# SNES-1Chip_MR_QID.net
KiCad netlist of a schematic drawn in EAGLE
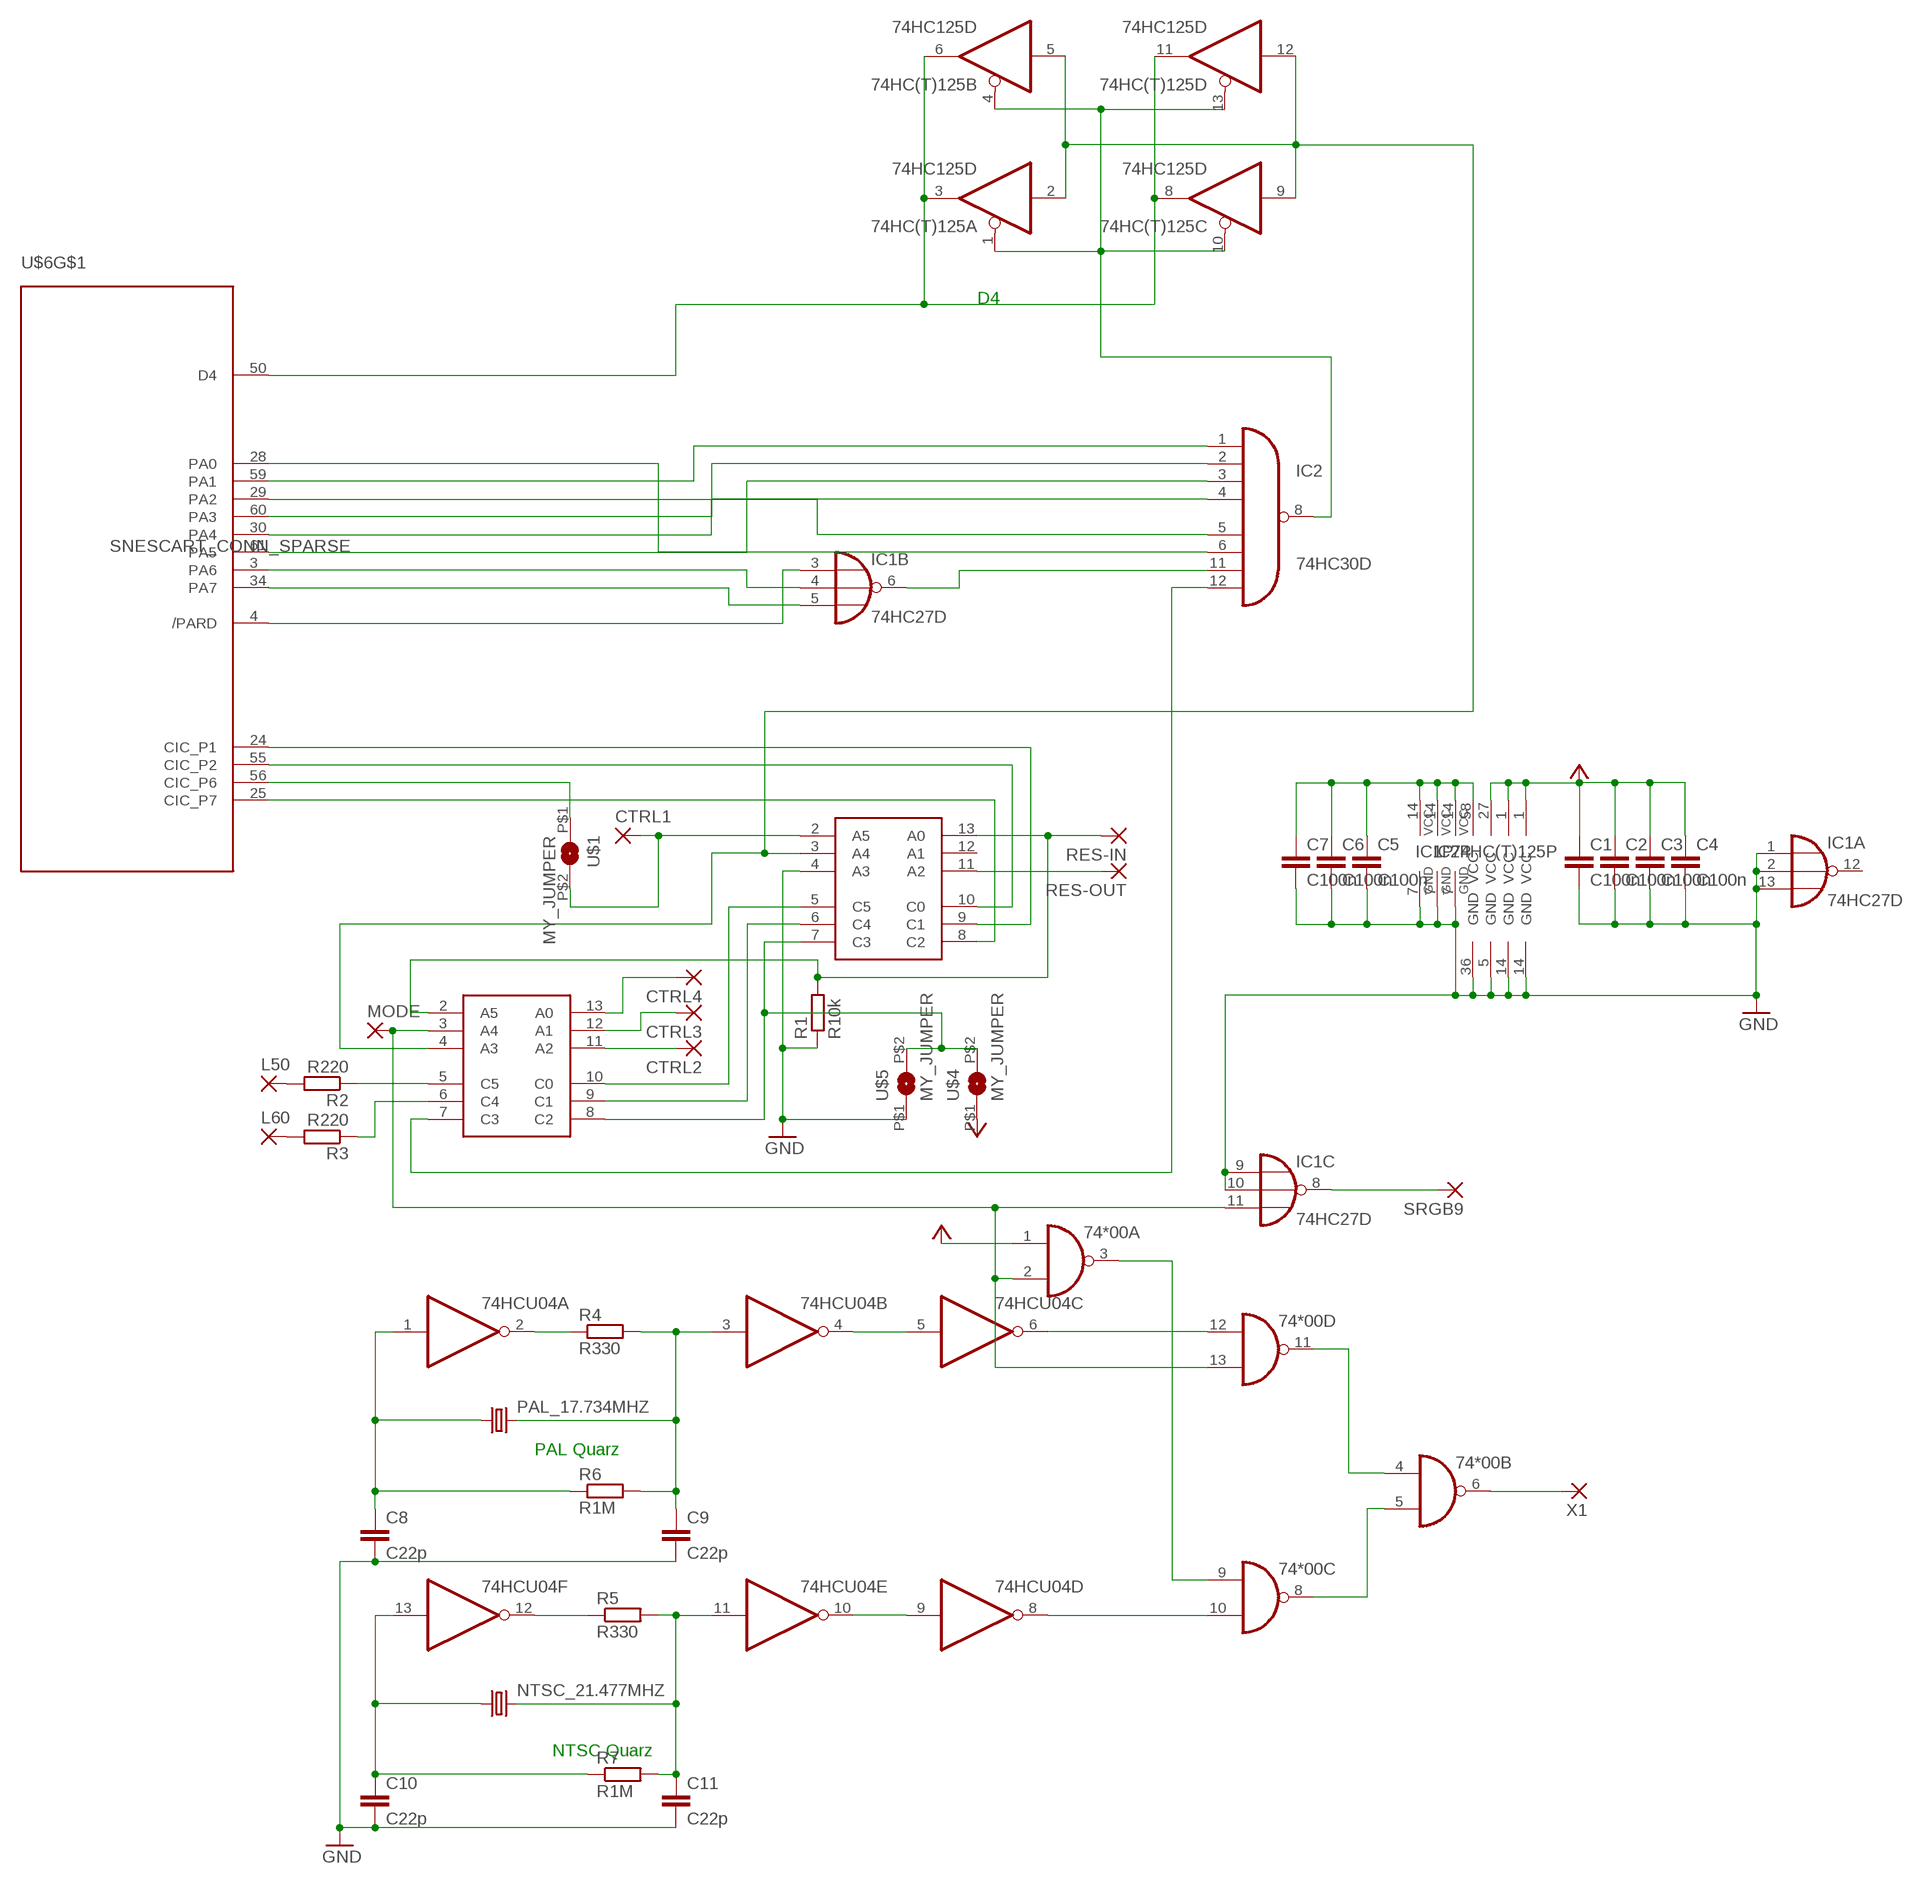
[diagram p0: schematic, sheet 1]

(export (version "E")
  (design (tool "Eeschema 10.0.6"))
  (components
    (comp (ref "74*00")
      (value "7400D")
      (footprint "eagle-import:SO14")
      (libsource (lib "eagle-import") (part "7400D"))
    )
    (comp (ref "74HC(T)125")
      (value "74HC125D")
      (footprint "eagle-import:SO14")
      (libsource (lib "eagle-import") (part "74125DHC"))
    )
    (comp (ref "74HCU04")
      (value "74HC04D")
      (footprint "eagle-import:SO14")
      (libsource (lib "eagle-import") (part "7404DHC"))
    )
    (comp (ref "C1")
      (value "C100n")
      (footprint "eagle-import:Z0805")
      (libsource (lib "eagle-import") (part "C0805"))
    )
    (comp (ref "C2")
      (value "C100n")
      (footprint "eagle-import:Z0805")
      (libsource (lib "eagle-import") (part "C0805"))
    )
    (comp (ref "C3")
      (value "C100n")
      (footprint "eagle-import:Z0805")
      (libsource (lib "eagle-import") (part "C0805"))
    )
    (comp (ref "C4")
      (value "C100n")
      (footprint "eagle-import:Z0805")
      (libsource (lib "eagle-import") (part "C0805"))
    )
    (comp (ref "C5")
      (value "C100n")
      (footprint "eagle-import:Z0805")
      (libsource (lib "eagle-import") (part "C0805"))
    )
    (comp (ref "C6")
      (value "C100n")
      (footprint "eagle-import:Z0805")
      (libsource (lib "eagle-import") (part "C0805"))
    )
    (comp (ref "C7")
      (value "C100n")
      (footprint "eagle-import:Z0805")
      (libsource (lib "eagle-import") (part "C0805"))
    )
    (comp (ref "C8")
      (value "C22p")
      (footprint "eagle-import:Z0805")
      (libsource (lib "eagle-import") (part "C0805"))
    )
    (comp (ref "C9")
      (value "C22p")
      (footprint "eagle-import:Z0805")
      (libsource (lib "eagle-import") (part "C0805"))
    )
    (comp (ref "C10")
      (value "C22p")
      (footprint "eagle-import:Z0805")
      (libsource (lib "eagle-import") (part "C0805"))
    )
    (comp (ref "C11")
      (value "C22p")
      (footprint "eagle-import:Z0805")
      (libsource (lib "eagle-import") (part "C0805"))
    )
    (comp (ref "CTRL1")
      (value "SMD2")
      (footprint "eagle-import:SMD1,27-2,54")
      (libsource (lib "eagle-import") (part "SMD2"))
    )
    (comp (ref "CTRL2")
      (value "SMD2")
      (footprint "eagle-import:SMD1,27-2,54")
      (libsource (lib "eagle-import") (part "SMD2"))
    )
    (comp (ref "CTRL3")
      (value "SMD2")
      (footprint "eagle-import:SMD1,27-2,54")
      (libsource (lib "eagle-import") (part "SMD2"))
    )
    (comp (ref "CTRL4")
      (value "SMD2")
      (footprint "eagle-import:SMD1,27-2,54")
      (libsource (lib "eagle-import") (part "SMD2"))
    )
    (comp (ref "IC1")
      (value "74HC27D")
      (footprint "eagle-import:SO14")
      (libsource (lib "eagle-import") (part "7427DHC"))
    )
    (comp (ref "IC2")
      (value "74HC30D")
      (footprint "eagle-import:SO14")
      (libsource (lib "eagle-import") (part "7430DHC"))
    )
    (comp (ref "L50")
      (value "SMD2")
      (footprint "eagle-import:SMD1,27-2,54")
      (libsource (lib "eagle-import") (part "SMD2"))
    )
    (comp (ref "L60")
      (value "SMD2")
      (footprint "eagle-import:SMD1,27-2,54")
      (libsource (lib "eagle-import") (part "SMD2"))
    )
    (comp (ref "MODE")
      (value "SMD2")
      (footprint "eagle-import:SMD1,27-2,54")
      (libsource (lib "eagle-import") (part "SMD2"))
    )
    (comp (ref "NTSC_21.477MHZ")
      (value "CRYSTALHC49UP")
      (footprint "eagle-import:HC49UP")
      (libsource (lib "eagle-import") (part "CRYSTALHC49UP"))
    )
    (comp (ref "PAL_17.734MHZ")
      (value "CRYSTALHC49UP")
      (footprint "eagle-import:HC49UP")
      (libsource (lib "eagle-import") (part "CRYSTALHC49UP"))
    )
    (comp (ref "R1")
      (value "R10k")
      (footprint "eagle-import:Z0805")
      (libsource (lib "eagle-import") (part "R0805"))
    )
    (comp (ref "R2")
      (value "R220")
      (footprint "eagle-import:Z0805")
      (libsource (lib "eagle-import") (part "R0805"))
    )
    (comp (ref "R3")
      (value "R220")
      (footprint "eagle-import:Z0805")
      (libsource (lib "eagle-import") (part "R0805"))
    )
    (comp (ref "R4")
      (value "R330")
      (footprint "eagle-import:Z0805")
      (libsource (lib "eagle-import") (part "R0805"))
    )
    (comp (ref "R5")
      (value "R330")
      (footprint "eagle-import:Z0805")
      (libsource (lib "eagle-import") (part "R0805"))
    )
    (comp (ref "R6")
      (value "R1M")
      (footprint "eagle-import:Z0805")
      (libsource (lib "eagle-import") (part "R0805"))
    )
    (comp (ref "R7")
      (value "R1M")
      (footprint "eagle-import:Z0805")
      (libsource (lib "eagle-import") (part "R0805"))
    )
    (comp (ref "RES-IN")
      (value "SMD2")
      (footprint "eagle-import:SMD1,27-2,54")
      (libsource (lib "eagle-import") (part "SMD2"))
    )
    (comp (ref "RES-OUT")
      (value "SMD2")
      (footprint "eagle-import:SMD1,27-2,54")
      (libsource (lib "eagle-import") (part "SMD2"))
    )
    (comp (ref "SRGB9")
      (value "SMD2")
      (footprint "eagle-import:SMD1,27-2,54")
      (libsource (lib "eagle-import") (part "SMD2"))
    )
    (comp (ref "U$1")
      (value "MY_JUMPER")
      (footprint "eagle-import:MYJUMP")
      (libsource (lib "eagle-import") (part "MY_JUMPER"))
    )
    (comp (ref "U$2")
      (value "PIC16F630_SIMPLE")
      (footprint "eagle-import:PIC16F630")
      (libsource (lib "eagle-import") (part "PIC16F630_SIMPLE"))
    )
    (comp (ref "U$3")
      (value "PIC16F630_SIMPLE")
      (footprint "eagle-import:PIC16F630")
      (libsource (lib "eagle-import") (part "PIC16F630_SIMPLE"))
    )
    (comp (ref "U$4")
      (value "MY_JUMPER")
      (footprint "eagle-import:MYJUMP")
      (libsource (lib "eagle-import") (part "MY_JUMPER"))
    )
    (comp (ref "U$5")
      (value "MY_JUMPER")
      (footprint "eagle-import:MYJUMP")
      (libsource (lib "eagle-import") (part "MY_JUMPER"))
    )
    (comp (ref "U$6")
      (value "SNESCART_CONN_SPARSE")
      (footprint "eagle-import:SNESCART_CONN_SPARSE")
      (libsource (lib "eagle-import") (part "SNESCART_CONN_SPARSE"))
    )
    (comp (ref "X1")
      (value "SMD2")
      (footprint "eagle-import:SMD1,27-2,54")
      (libsource (lib "eagle-import") (part "SMD2"))
    )
  )
  (nets
    (net (code "1") (name "+5V") (class "Default")
      (node (ref "74*00") (pin "1") (pinfunction "I0_1") (pintype "input"))
      (node (ref "C1") (pin "1") (pinfunction "1_1") (pintype "passive"))
      (node (ref "C2") (pin "1") (pinfunction "1_1") (pintype "passive"))
      (node (ref "C3") (pin "1") (pinfunction "1_1") (pintype "passive"))
      (node (ref "C4") (pin "1") (pinfunction "1_1") (pintype "passive"))
      (node (ref "U$2") (pin "1") (pinfunction "VCC_1") (pintype "bidirectional"))
      (node (ref "U$3") (pin "1") (pinfunction "VCC_1") (pintype "bidirectional"))
      (node (ref "U$4") (pin "P$1") (pinfunction "1_P$1") (pintype "passive"))
      (node (ref "U$6") (pin "27") (pinfunction "VCC_27") (pintype "bidirectional"))
    )
    (net (code "2") (name "GND") (class "Default")
      (node (ref "74HC(T)125") (pin "7") (pinfunction "GND_7") (pintype "power_in"))
      (node (ref "C1") (pin "2") (pinfunction "2_2") (pintype "passive"))
      (node (ref "C10") (pin "2") (pinfunction "2_2") (pintype "passive"))
      (node (ref "C11") (pin "2") (pinfunction "2_2") (pintype "passive"))
      (node (ref "C2") (pin "2") (pinfunction "2_2") (pintype "passive"))
      (node (ref "C3") (pin "2") (pinfunction "2_2") (pintype "passive"))
      (node (ref "C4") (pin "2") (pinfunction "2_2") (pintype "passive"))
      (node (ref "C5") (pin "2") (pinfunction "2_2") (pintype "passive"))
      (node (ref "C6") (pin "2") (pinfunction "2_2") (pintype "passive"))
      (node (ref "C7") (pin "2") (pinfunction "2_2") (pintype "passive"))
      (node (ref "C8") (pin "2") (pinfunction "2_2") (pintype "passive"))
      (node (ref "C9") (pin "2") (pinfunction "2_2") (pintype "passive"))
      (node (ref "IC1") (pin "1") (pinfunction "I0_1") (pintype "input"))
      (node (ref "IC1") (pin "10") (pinfunction "I1_10") (pintype "input"))
      (node (ref "IC1") (pin "13") (pinfunction "I2_13") (pintype "input"))
      (node (ref "IC1") (pin "2") (pinfunction "I1_2") (pintype "input"))
      (node (ref "IC1") (pin "7") (pinfunction "GND_7") (pintype "power_in"))
      (node (ref "IC1") (pin "9") (pinfunction "I0_9") (pintype "input"))
      (node (ref "IC2") (pin "7") (pinfunction "GND_7") (pintype "power_in"))
      (node (ref "R1") (pin "1") (pinfunction "1_1") (pintype "passive"))
      (node (ref "U$2") (pin "14") (pinfunction "GND_14") (pintype "bidirectional"))
      (node (ref "U$2") (pin "4") (pinfunction "A3_4") (pintype "bidirectional"))
      (node (ref "U$3") (pin "14") (pinfunction "GND_14") (pintype "bidirectional"))
      (node (ref "U$5") (pin "P$1") (pinfunction "1_P$1") (pintype "passive"))
      (node (ref "U$6") (pin "36") (pinfunction "GND_36") (pintype "bidirectional"))
      (node (ref "U$6") (pin "5") (pinfunction "GND_5") (pintype "bidirectional"))
    )
    (net (code "3") (name "Net-(74*00A-I1)") (class "Default")
      (node (ref "74*00") (pin "13") (pinfunction "I1_13") (pintype "input"))
      (node (ref "74*00") (pin "2") (pinfunction "I1_2") (pintype "input"))
      (node (ref "IC1") (pin "11") (pinfunction "I2_11") (pintype "input"))
      (node (ref "MODE") (pin "1") (pinfunction "P_1") (pintype "passive"))
      (node (ref "U$3") (pin "3") (pinfunction "A4_3") (pintype "bidirectional"))
    )
    (net (code "4") (name "Net-(74*00A-O)") (class "Default")
      (node (ref "74*00") (pin "3") (pinfunction "O_3") (pintype "output"))
      (node (ref "74*00") (pin "9") (pinfunction "I0_9") (pintype "input"))
    )
    (net (code "5") (name "Net-(74*00B-I0)") (class "Default")
      (node (ref "74*00") (pin "11") (pinfunction "O_11") (pintype "output"))
      (node (ref "74*00") (pin "4") (pinfunction "I0_4") (pintype "input"))
    )
    (net (code "6") (name "Net-(74*00B-I1)") (class "Default")
      (node (ref "74*00") (pin "5") (pinfunction "I1_5") (pintype "input"))
      (node (ref "74*00") (pin "8") (pinfunction "O_8") (pintype "output"))
    )
    (net (code "7") (name "Net-(74*00B-O)") (class "Default")
      (node (ref "74*00") (pin "6") (pinfunction "O_6") (pintype "output"))
      (node (ref "X1") (pin "1") (pinfunction "P_1") (pintype "passive"))
    )
    (net (code "8") (name "Net-(74*00C-I1)") (class "Default")
      (node (ref "74*00") (pin "10") (pinfunction "I1_10") (pintype "input"))
      (node (ref "74HCU04") (pin "8") (pinfunction "O_8") (pintype "output"))
    )
    (net (code "9") (name "Net-(74*00D-I0)") (class "Default")
      (node (ref "74*00") (pin "12") (pinfunction "I0_12") (pintype "input"))
      (node (ref "74HCU04") (pin "6") (pinfunction "O_6") (pintype "output"))
    )
    (net (code "10") (name "Net-(74HC(T)125A-I)") (class "Default")
      (node (ref "74HC(T)125") (pin "12") (pinfunction "I_12") (pintype "input"))
      (node (ref "74HC(T)125") (pin "2") (pinfunction "I_2") (pintype "input"))
      (node (ref "74HC(T)125") (pin "5") (pinfunction "I_5") (pintype "input"))
      (node (ref "74HC(T)125") (pin "9") (pinfunction "I_9") (pintype "input"))
      (node (ref "U$2") (pin "3") (pinfunction "A4_3") (pintype "bidirectional"))
      (node (ref "U$3") (pin "4") (pinfunction "A3_4") (pintype "bidirectional"))
    )
    (net (code "11") (name "Net-(74HC(T)125A-O)") (class "Default")
      (node (ref "74HC(T)125") (pin "11") (pinfunction "O_11") (pintype "tri_state"))
      (node (ref "74HC(T)125") (pin "3") (pinfunction "O_3") (pintype "tri_state"))
      (node (ref "74HC(T)125") (pin "6") (pinfunction "O_6") (pintype "tri_state"))
      (node (ref "74HC(T)125") (pin "8") (pinfunction "O_8") (pintype "tri_state"))
      (node (ref "U$6") (pin "50") (pinfunction "D4_50") (pintype "bidirectional"))
    )
    (net (code "12") (name "Net-(74HC(T)125A-OE)") (class "Default")
      (node (ref "74HC(T)125") (pin "1") (pinfunction "OE_1") (pintype "input"))
      (node (ref "74HC(T)125") (pin "10") (pinfunction "OE_10") (pintype "input"))
      (node (ref "74HC(T)125") (pin "13") (pinfunction "OE_13") (pintype "input"))
      (node (ref "74HC(T)125") (pin "4") (pinfunction "OE_4") (pintype "input"))
      (node (ref "IC2") (pin "8") (pinfunction "O_8") (pintype "output"))
    )
    (net (code "13") (name "Net-(74HC(T)125E-VCC)") (class "Default")
      (node (ref "74HC(T)125") (pin "14") (pinfunction "VCC_14") (pintype "power_in"))
      (node (ref "C5") (pin "1") (pinfunction "1_1") (pintype "passive"))
      (node (ref "C6") (pin "1") (pinfunction "1_1") (pintype "passive"))
      (node (ref "C7") (pin "1") (pinfunction "1_1") (pintype "passive"))
      (node (ref "IC1") (pin "14") (pinfunction "VCC_14") (pintype "power_in"))
      (node (ref "IC2") (pin "14") (pinfunction "VCC_14") (pintype "power_in"))
      (node (ref "U$6") (pin "58") (pinfunction "VCC_58") (pintype "bidirectional"))
    )
    (net (code "14") (name "Net-(74HCU04A-I)") (class "Default")
      (node (ref "74HCU04") (pin "1") (pinfunction "I_1") (pintype "input"))
      (node (ref "C8") (pin "1") (pinfunction "1_1") (pintype "passive"))
      (node (ref "PAL_17.734MHZ") (pin "1") (pinfunction "1_1") (pintype "passive"))
      (node (ref "R6") (pin "1") (pinfunction "1_1") (pintype "passive"))
    )
    (net (code "15") (name "Net-(74HCU04A-O)") (class "Default")
      (node (ref "74HCU04") (pin "2") (pinfunction "O_2") (pintype "output"))
      (node (ref "R4") (pin "1") (pinfunction "1_1") (pintype "passive"))
    )
    (net (code "16") (name "Net-(74HCU04B-I)") (class "Default")
      (node (ref "74HCU04") (pin "3") (pinfunction "I_3") (pintype "input"))
      (node (ref "C9") (pin "1") (pinfunction "1_1") (pintype "passive"))
      (node (ref "PAL_17.734MHZ") (pin "2") (pinfunction "2_2") (pintype "passive"))
      (node (ref "R4") (pin "2") (pinfunction "2_2") (pintype "passive"))
      (node (ref "R6") (pin "2") (pinfunction "2_2") (pintype "passive"))
    )
    (net (code "17") (name "Net-(74HCU04B-O)") (class "Default")
      (node (ref "74HCU04") (pin "4") (pinfunction "O_4") (pintype "output"))
      (node (ref "74HCU04") (pin "5") (pinfunction "I_5") (pintype "input"))
    )
    (net (code "18") (name "Net-(74HCU04D-I)") (class "Default")
      (node (ref "74HCU04") (pin "10") (pinfunction "O_10") (pintype "output"))
      (node (ref "74HCU04") (pin "9") (pinfunction "I_9") (pintype "input"))
    )
    (net (code "19") (name "Net-(74HCU04E-I)") (class "Default")
      (node (ref "74HCU04") (pin "11") (pinfunction "I_11") (pintype "input"))
      (node (ref "C11") (pin "1") (pinfunction "1_1") (pintype "passive"))
      (node (ref "NTSC_21.477MHZ") (pin "2") (pinfunction "2_2") (pintype "passive"))
      (node (ref "R5") (pin "2") (pinfunction "2_2") (pintype "passive"))
      (node (ref "R7") (pin "2") (pinfunction "2_2") (pintype "passive"))
    )
    (net (code "20") (name "Net-(74HCU04F-I)") (class "Default")
      (node (ref "74HCU04") (pin "13") (pinfunction "I_13") (pintype "input"))
      (node (ref "C10") (pin "1") (pinfunction "1_1") (pintype "passive"))
      (node (ref "NTSC_21.477MHZ") (pin "1") (pinfunction "1_1") (pintype "passive"))
      (node (ref "R7") (pin "1") (pinfunction "1_1") (pintype "passive"))
    )
    (net (code "21") (name "Net-(74HCU04F-O)") (class "Default")
      (node (ref "74HCU04") (pin "12") (pinfunction "O_12") (pintype "output"))
      (node (ref "R5") (pin "1") (pinfunction "1_1") (pintype "passive"))
    )
    (net (code "22") (name "Net-(CTRL1-P)") (class "Default")
      (node (ref "CTRL1") (pin "1") (pinfunction "P_1") (pintype "passive"))
      (node (ref "U$1") (pin "P$2") (pinfunction "2_P$2") (pintype "passive"))
      (node (ref "U$2") (pin "2") (pinfunction "A5_2") (pintype "bidirectional"))
    )
    (net (code "23") (name "Net-(CTRL2-P)") (class "Default")
      (node (ref "CTRL2") (pin "1") (pinfunction "P_1") (pintype "passive"))
      (node (ref "U$3") (pin "11") (pinfunction "A2_11") (pintype "bidirectional"))
    )
    (net (code "24") (name "Net-(CTRL3-P)") (class "Default")
      (node (ref "CTRL3") (pin "1") (pinfunction "P_1") (pintype "passive"))
      (node (ref "U$3") (pin "12") (pinfunction "A1_12") (pintype "bidirectional"))
    )
    (net (code "25") (name "Net-(CTRL4-P)") (class "Default")
      (node (ref "CTRL4") (pin "1") (pinfunction "P_1") (pintype "passive"))
      (node (ref "U$3") (pin "13") (pinfunction "A0_13") (pintype "bidirectional"))
    )
    (net (code "26") (name "Net-(IC1B-I0)") (class "Default")
      (node (ref "IC1") (pin "3") (pinfunction "I0_3") (pintype "input"))
      (node (ref "U$6") (pin "4") (pinfunction "/PARD_4") (pintype "bidirectional"))
    )
    (net (code "27") (name "Net-(IC1B-I1)") (class "Default")
      (node (ref "IC1") (pin "4") (pinfunction "I1_4") (pintype "input"))
      (node (ref "U$6") (pin "3") (pinfunction "PA6_3") (pintype "bidirectional"))
    )
    (net (code "28") (name "Net-(IC1B-I2)") (class "Default")
      (node (ref "IC1") (pin "5") (pinfunction "I2_5") (pintype "input"))
      (node (ref "U$6") (pin "34") (pinfunction "PA7_34") (pintype "bidirectional"))
    )
    (net (code "29") (name "Net-(IC1B-O)") (class "Default")
      (node (ref "IC1") (pin "6") (pinfunction "O_6") (pintype "output"))
      (node (ref "IC2") (pin "11") (pinfunction "I6_11") (pintype "input"))
    )
    (net (code "30") (name "Net-(IC1C-O)") (class "Default")
      (node (ref "IC1") (pin "8") (pinfunction "O_8") (pintype "output"))
      (node (ref "SRGB9") (pin "1") (pinfunction "P_1") (pintype "passive"))
    )
    (net (code "31") (name "Net-(IC2A-I0)") (class "Default")
      (node (ref "IC2") (pin "1") (pinfunction "I0_1") (pintype "input"))
      (node (ref "U$6") (pin "59") (pinfunction "PA1_59") (pintype "bidirectional"))
    )
    (net (code "32") (name "Net-(IC2A-I1)") (class "Default")
      (node (ref "IC2") (pin "2") (pinfunction "I1_2") (pintype "input"))
      (node (ref "U$6") (pin "60") (pinfunction "PA3_60") (pintype "bidirectional"))
    )
    (net (code "33") (name "Net-(IC2A-I2)") (class "Default")
      (node (ref "IC2") (pin "3") (pinfunction "I2_3") (pintype "input"))
      (node (ref "U$6") (pin "61") (pinfunction "PA5_61") (pintype "bidirectional"))
    )
    (net (code "34") (name "Net-(IC2A-I3)") (class "Default")
      (node (ref "IC2") (pin "4") (pinfunction "I3_4") (pintype "input"))
      (node (ref "U$6") (pin "30") (pinfunction "PA4_30") (pintype "bidirectional"))
    )
    (net (code "35") (name "Net-(IC2A-I4)") (class "Default")
      (node (ref "IC2") (pin "5") (pinfunction "I4_5") (pintype "input"))
      (node (ref "U$6") (pin "29") (pinfunction "PA2_29") (pintype "bidirectional"))
    )
    (net (code "36") (name "Net-(IC2A-I5)") (class "Default")
      (node (ref "IC2") (pin "6") (pinfunction "I5_6") (pintype "input"))
      (node (ref "U$6") (pin "28") (pinfunction "PA0_28") (pintype "bidirectional"))
    )
    (net (code "37") (name "Net-(IC2A-I7)") (class "Default")
      (node (ref "IC2") (pin "12") (pinfunction "I7_12") (pintype "input"))
      (node (ref "U$3") (pin "7") (pinfunction "C3_7") (pintype "bidirectional"))
    )
    (net (code "38") (name "Net-(L50-P)") (class "Default")
      (node (ref "L50") (pin "1") (pinfunction "P_1") (pintype "passive"))
      (node (ref "R2") (pin "2") (pinfunction "2_2") (pintype "passive"))
    )
    (net (code "39") (name "Net-(L60-P)") (class "Default")
      (node (ref "L60") (pin "1") (pinfunction "P_1") (pintype "passive"))
      (node (ref "R3") (pin "2") (pinfunction "2_2") (pintype "passive"))
    )
    (net (code "40") (name "Net-(RES-IN-P)") (class "Default")
      (node (ref "R1") (pin "2") (pinfunction "2_2") (pintype "passive"))
      (node (ref "RES-IN") (pin "1") (pinfunction "P_1") (pintype "passive"))
      (node (ref "U$2") (pin "13") (pinfunction "A0_13") (pintype "bidirectional"))
      (node (ref "U$3") (pin "2") (pinfunction "A5_2") (pintype "bidirectional"))
    )
    (net (code "41") (name "Net-(RES-OUT-P)") (class "Default")
      (node (ref "RES-OUT") (pin "1") (pinfunction "P_1") (pintype "passive"))
      (node (ref "U$2") (pin "11") (pinfunction "A2_11") (pintype "bidirectional"))
    )
    (net (code "42") (name "Net-(U$1-1)") (class "Default")
      (node (ref "U$1") (pin "P$1") (pinfunction "1_P$1") (pintype "passive"))
      (node (ref "U$6") (pin "56") (pinfunction "CIC_P6_56") (pintype "bidirectional"))
    )
    (net (code "43") (name "Net-(U$2A-C0)") (class "Default")
      (node (ref "U$2") (pin "10") (pinfunction "C0_10") (pintype "bidirectional"))
      (node (ref "U$6") (pin "55") (pinfunction "CIC_P2_55") (pintype "bidirectional"))
    )
    (net (code "44") (name "Net-(U$2A-C1)") (class "Default")
      (node (ref "U$2") (pin "9") (pinfunction "C1_9") (pintype "bidirectional"))
      (node (ref "U$6") (pin "24") (pinfunction "CIC_P1_24") (pintype "bidirectional"))
    )
    (net (code "45") (name "Net-(U$2A-C2)") (class "Default")
      (node (ref "U$2") (pin "8") (pinfunction "C2_8") (pintype "bidirectional"))
      (node (ref "U$6") (pin "25") (pinfunction "CIC_P7_25") (pintype "bidirectional"))
    )
    (net (code "46") (name "Net-(U$2A-C3)") (class "Default")
      (node (ref "U$2") (pin "7") (pinfunction "C3_7") (pintype "bidirectional"))
      (node (ref "U$3") (pin "8") (pinfunction "C2_8") (pintype "bidirectional"))
      (node (ref "U$4") (pin "P$2") (pinfunction "2_P$2") (pintype "passive"))
      (node (ref "U$5") (pin "P$2") (pinfunction "2_P$2") (pintype "passive"))
    )
    (net (code "47") (name "Net-(U$2A-C4)") (class "Default")
      (node (ref "U$2") (pin "6") (pinfunction "C4_6") (pintype "bidirectional"))
      (node (ref "U$3") (pin "9") (pinfunction "C1_9") (pintype "bidirectional"))
    )
    (net (code "48") (name "Net-(U$2A-C5)") (class "Default")
      (node (ref "U$2") (pin "5") (pinfunction "C5_5") (pintype "bidirectional"))
      (node (ref "U$3") (pin "10") (pinfunction "C0_10") (pintype "bidirectional"))
    )
    (net (code "49") (name "Net-(U$3A-C4)") (class "Default")
      (node (ref "R3") (pin "1") (pinfunction "1_1") (pintype "passive"))
      (node (ref "U$3") (pin "6") (pinfunction "C4_6") (pintype "bidirectional"))
    )
    (net (code "50") (name "Net-(U$3A-C5)") (class "Default")
      (node (ref "R2") (pin "1") (pinfunction "1_1") (pintype "passive"))
      (node (ref "U$3") (pin "5") (pinfunction "C5_5") (pintype "bidirectional"))
    )
    (net (code "51") (name "unconnected-(IC1A-O-Pad12)") (class "Default")
      (node (ref "IC1") (pin "12") (pinfunction "O_12") (pintype "output"))
    )
    (net (code "52") (name "unconnected-(U$2A-A1-Pad12)") (class "Default")
      (node (ref "U$2") (pin "12") (pinfunction "A1_12") (pintype "bidirectional"))
    )
  )
)
